# 7-segmentSchematic.net
KiCad netlist of a schematic drawn in Altium Designer
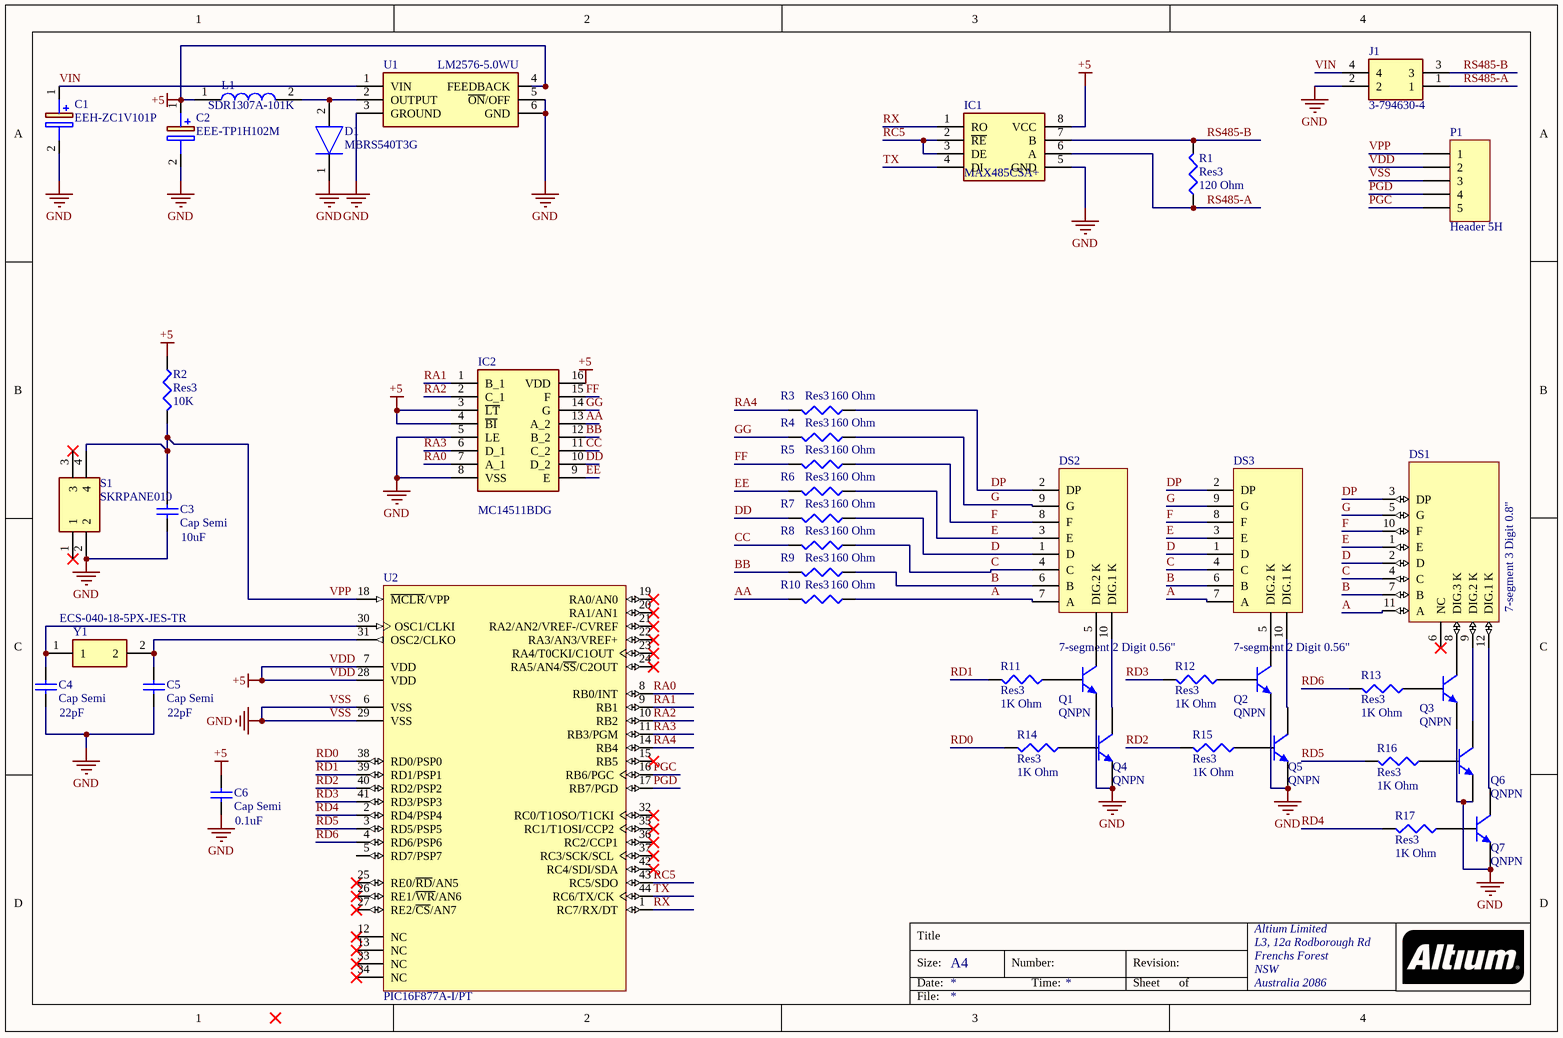
[diagram p0: 7-segmentSchematic.SchDoc]

(export (version "E")
  (design (tool "Eeschema 10.0.6"))
  (components
    (comp (ref "C1")
      (value "EEH-ZC1V101P")
      (footprint "SamacSys:CAPAE830X1050N")
      (description "Capacitor Polarised")
      (fields (field (name "MOUSER PART NUMBER") "667-EEH-ZC1V101P"))
      (libsource (lib "*") (part "EEH-ZC1V101P"))
    )
    (comp (ref "C2")
      (value "EEE-TP1H102M")
      (footprint "SamacSys:CAPAE1900X1700N")
      (description "Capacitor Polarised")
      (fields (field (name "MOUSER PART NUMBER") "667-EEE-TP1H102M"))
      (libsource (lib "*") (part "EEE-TP1H102M"))
    )
    (comp (ref "C3")
      (value "Cap Semi")
      (footprint "C1206")
      (description "Capacitor (Semiconductor SIM Model)")
      (fields (field (name "ALTIUM_VALUE") "10uF") (field (name "PUBLISHER") "Altium Limited"))
      (libsource (lib "Miscellaneous Devices") (part "Cap Semi"))
    )
    (comp (ref "C4")
      (value "Cap Semi")
      (footprint "C1206")
      (description "Capacitor (Semiconductor SIM Model)")
      (fields (field (name "ALTIUM_VALUE") "22pF") (field (name "PUBLISHER") "Altium Limited"))
      (libsource (lib "Miscellaneous Devices") (part "Cap Semi"))
    )
    (comp (ref "C5")
      (value "Cap Semi")
      (footprint "C1206")
      (description "Capacitor (Semiconductor SIM Model)")
      (fields (field (name "ALTIUM_VALUE") "22pF") (field (name "PUBLISHER") "Altium Limited"))
      (libsource (lib "Miscellaneous Devices") (part "Cap Semi"))
    )
    (comp (ref "C6")
      (value "Cap Semi")
      (footprint "C1206")
      (description "Capacitor (Semiconductor SIM Model)")
      (fields (field (name "ALTIUM_VALUE") "0.1uF") (field (name "PUBLISHER") "Altium Limited"))
      (libsource (lib "Miscellaneous Devices") (part "Cap Semi"))
    )
    (comp (ref "D1")
      (value "MBRS540T3G")
      (footprint "SamacSys:DIOM7958X256N")
      (description "Diode")
      (fields (field (name "MOUSER PART NUMBER") "863-MBRS540T3G") (field (name "RS PART NUMBER") "6880512P"))
      (libsource (lib "*") (part "MBRS540T3G"))
    )
    (comp (ref "DS1")
      (value "7-segment 3 Digit 0.8\"")
      (footprint "7-segment 3Digit")
      (libsource (lib "7-segment-3Digit") (part "7-segment 3 Digit"))
    )
    (comp (ref "DS2")
      (value "7-segment 2 Digit 0.56\"")
      (footprint "7-segment 2Digit")
      (libsource (lib "7-segment-3Digit") (part "7-segment 2 Digit"))
    )
    (comp (ref "DS3")
      (value "7-segment 2 Digit 0.56\"")
      (footprint "7-segment 2Digit")
      (libsource (lib "7-segment-3Digit") (part "7-segment 2 Digit"))
    )
    (comp (ref "IC1")
      (value "MAX485CSA+")
      (footprint "SamacSys:SOIC127P600X175-8N")
      (description "Integrated Circuit")
      (fields (field (name "MOUSER PART NUMBER") "700-MAX485CSA") (field (name "RS PART NUMBER") "5404564P"))
      (libsource (lib "*") (part "MAX485CSA+"))
    )
    (comp (ref "IC2")
      (value "MC14511BDG")
      (footprint "SamacSys:SOIC127P600X175-16N")
      (description "Integrated Circuit")
      (fields (field (name "MOUSER PART NUMBER") "863-MC14511BDG") (field (name "RS PART NUMBER") "8063267P"))
      (libsource (lib "*") (part "MC14511BDG"))
    )
    (comp (ref "J1")
      (value "3-794630-4")
      (footprint "SamacSys:37946304")
      (description "Connector")
      (fields (field (name "MOUSER PART NUMBER") "571-3-794630-4") (field (name "RS PART NUMBER") "4959344P"))
      (libsource (lib "*") (part "3-794630-4"))
    )
    (comp (ref "L1")
      (value "SDR1307A-101K")
      (footprint "SamacSys:SDR1307A101K")
      (description "Inductor")
      (fields (field (name "MOUSER PART NUMBER") "652-SDR1307A-101K"))
      (libsource (lib "*") (part "SDR1307A-101K"))
    )
    (comp (ref "P1")
      (value "Header 5H")
      (footprint "HDR1X5H")
      (description "Header, 5-Pin, Right Angle")
      (fields (field (name "PUBLISHER") "Altium Limited"))
      (libsource (lib "Miscellaneous Connectors") (part "Header 5H"))
    )
    (comp (ref "Q1")
      (value "QNPN")
      (footprint "SOT-23B_L")
      (description "NPN Bipolar Transistor")
      (fields (field (name "PUBLISHER") "Altium Limited"))
      (libsource (lib "Miscellaneous Devices") (part "QNPN"))
    )
    (comp (ref "Q2")
      (value "QNPN")
      (footprint "SOT-23B_L")
      (description "NPN Bipolar Transistor")
      (fields (field (name "PUBLISHER") "Altium Limited"))
      (libsource (lib "Miscellaneous Devices") (part "QNPN"))
    )
    (comp (ref "Q3")
      (value "QNPN")
      (footprint "SOT-23B_L")
      (description "NPN Bipolar Transistor")
      (fields (field (name "PUBLISHER") "Altium Limited"))
      (libsource (lib "Miscellaneous Devices") (part "QNPN"))
    )
    (comp (ref "Q4")
      (value "QNPN")
      (footprint "SOT-23B_L")
      (description "NPN Bipolar Transistor")
      (fields (field (name "PUBLISHER") "Altium Limited"))
      (libsource (lib "Miscellaneous Devices") (part "QNPN"))
    )
    (comp (ref "Q5")
      (value "QNPN")
      (footprint "SOT-23B_L")
      (description "NPN Bipolar Transistor")
      (fields (field (name "PUBLISHER") "Altium Limited"))
      (libsource (lib "Miscellaneous Devices") (part "QNPN"))
    )
    (comp (ref "Q6")
      (value "QNPN")
      (footprint "SOT-23B_L")
      (description "NPN Bipolar Transistor")
      (fields (field (name "PUBLISHER") "Altium Limited"))
      (libsource (lib "Miscellaneous Devices") (part "QNPN"))
    )
    (comp (ref "Q7")
      (value "QNPN")
      (footprint "SOT-23B_L")
      (description "NPN Bipolar Transistor")
      (fields (field (name "PUBLISHER") "Altium Limited"))
      (libsource (lib "Miscellaneous Devices") (part "QNPN"))
    )
    (comp (ref "R1")
      (value "Res3")
      (footprint "J1-0603")
      (description "Resistor")
      (fields (field (name "ALTIUM_VALUE") "120 Ohm") (field (name "PUBLISHER") "Altium Limited"))
      (libsource (lib "Miscellaneous Devices") (part "Res3"))
    )
    (comp (ref "R2")
      (value "Res3")
      (footprint "J1-0603")
      (description "Resistor")
      (fields (field (name "ALTIUM_VALUE") "10K") (field (name "PUBLISHER") "Altium Limited"))
      (libsource (lib "Miscellaneous Devices") (part "Res3"))
    )
    (comp (ref "R3")
      (value "Res3")
      (footprint "12Z-2010")
      (description "Resistor")
      (fields (field (name "ALTIUM_VALUE") "160 Ohm") (field (name "PUBLISHER") "Altium Limited"))
      (libsource (lib "Miscellaneous Devices") (part "Res3"))
    )
    (comp (ref "R4")
      (value "Res3")
      (footprint "12Z-2010")
      (description "Resistor")
      (fields (field (name "ALTIUM_VALUE") "160 Ohm") (field (name "PUBLISHER") "Altium Limited"))
      (libsource (lib "Miscellaneous Devices") (part "Res3"))
    )
    (comp (ref "R5")
      (value "Res3")
      (footprint "12Z-2010")
      (description "Resistor")
      (fields (field (name "ALTIUM_VALUE") "160 Ohm") (field (name "PUBLISHER") "Altium Limited"))
      (libsource (lib "Miscellaneous Devices") (part "Res3"))
    )
    (comp (ref "R6")
      (value "Res3")
      (footprint "12Z-2010")
      (description "Resistor")
      (fields (field (name "ALTIUM_VALUE") "160 Ohm") (field (name "PUBLISHER") "Altium Limited"))
      (libsource (lib "Miscellaneous Devices") (part "Res3"))
    )
    (comp (ref "R7")
      (value "Res3")
      (footprint "12Z-2010")
      (description "Resistor")
      (fields (field (name "ALTIUM_VALUE") "160 Ohm") (field (name "PUBLISHER") "Altium Limited"))
      (libsource (lib "Miscellaneous Devices") (part "Res3"))
    )
    (comp (ref "R8")
      (value "Res3")
      (footprint "12Z-2010")
      (description "Resistor")
      (fields (field (name "ALTIUM_VALUE") "160 Ohm") (field (name "PUBLISHER") "Altium Limited"))
      (libsource (lib "Miscellaneous Devices") (part "Res3"))
    )
    (comp (ref "R9")
      (value "Res3")
      (footprint "12Z-2010")
      (description "Resistor")
      (fields (field (name "ALTIUM_VALUE") "160 Ohm") (field (name "PUBLISHER") "Altium Limited"))
      (libsource (lib "Miscellaneous Devices") (part "Res3"))
    )
    (comp (ref "R10")
      (value "Res3")
      (footprint "12Z-2010")
      (description "Resistor")
      (fields (field (name "ALTIUM_VALUE") "160 Ohm") (field (name "PUBLISHER") "Altium Limited"))
      (libsource (lib "Miscellaneous Devices") (part "Res3"))
    )
    (comp (ref "R11")
      (value "Res3")
      (footprint "J1-0603")
      (description "Resistor")
      (fields (field (name "ALTIUM_VALUE") "1K Ohm") (field (name "PUBLISHER") "Altium Limited"))
      (libsource (lib "Miscellaneous Devices") (part "Res3"))
    )
    (comp (ref "R12")
      (value "Res3")
      (footprint "J1-0603")
      (description "Resistor")
      (fields (field (name "ALTIUM_VALUE") "1K Ohm") (field (name "PUBLISHER") "Altium Limited"))
      (libsource (lib "Miscellaneous Devices") (part "Res3"))
    )
    (comp (ref "R13")
      (value "Res3")
      (footprint "J1-0603")
      (description "Resistor")
      (fields (field (name "ALTIUM_VALUE") "1K Ohm") (field (name "PUBLISHER") "Altium Limited"))
      (libsource (lib "Miscellaneous Devices") (part "Res3"))
    )
    (comp (ref "R14")
      (value "Res3")
      (footprint "J1-0603")
      (description "Resistor")
      (fields (field (name "ALTIUM_VALUE") "1K Ohm") (field (name "PUBLISHER") "Altium Limited"))
      (libsource (lib "Miscellaneous Devices") (part "Res3"))
    )
    (comp (ref "R15")
      (value "Res3")
      (footprint "J1-0603")
      (description "Resistor")
      (fields (field (name "ALTIUM_VALUE") "1K Ohm") (field (name "PUBLISHER") "Altium Limited"))
      (libsource (lib "Miscellaneous Devices") (part "Res3"))
    )
    (comp (ref "R16")
      (value "Res3")
      (footprint "J1-0603")
      (description "Resistor")
      (fields (field (name "ALTIUM_VALUE") "1K Ohm") (field (name "PUBLISHER") "Altium Limited"))
      (libsource (lib "Miscellaneous Devices") (part "Res3"))
    )
    (comp (ref "R17")
      (value "Res3")
      (footprint "J1-0603")
      (description "Resistor")
      (fields (field (name "ALTIUM_VALUE") "1K Ohm") (field (name "PUBLISHER") "Altium Limited"))
      (libsource (lib "Miscellaneous Devices") (part "Res3"))
    )
    (comp (ref "S1")
      (value "SKRPANE010")
      (footprint "SamacSys:SKRPADE010")
      (description "Switch")
      (fields (field (name "MOUSER PART NUMBER") "688-SKRPANE010"))
      (libsource (lib "*") (part "SKRPANE010"))
    )
    (comp (ref "U1")
      (value "LM2576-5.0WU")
      (footprint "SamacSys:MICROCHIP_TO-263")
      (description "Undefined or Miscellaneous")
      (fields
        (field (name "MOUSER PART NUMBER") "998-LM2576-5.0WU")
        (field (name "RS PART NUMBER") "9101925P")
      )
      (libsource (lib "*") (part "LM2576-5.0WU"))
    )
    (comp (ref "U2")
      (value "PIC16F877A-I/PT")
      (footprint "TQFP-PT44_N")
      (fields (field (name "PUBLISHER") "Altium Limited"))
      (libsource (lib "Microchip Microcontroller 8-Bit PIC16") (part "PIC16F877A-I/PT"))
    )
    (comp (ref "Y1")
      (value "ECS-040-18-5PX-JES-TR")
      (footprint "SamacSys:ECS49205PXTR")
      (description "Crystal or Oscillator")
      (fields (field (name "MOUSER PART NUMBER") "520-040-18-5PX-JEST"))
      (libsource (lib "*") (part "ECS-040-18-5PX-JES-TR"))
    )
  )
  (nets
    (net (code "1") (name "+5") (class "Default")
      (node (ref "C2") (pin "1") (pinfunction "+_1") (pintype "passive"))
      (node (ref "C6") (pin "2") (pinfunction "2_2") (pintype "passive"))
      (node (ref "IC1") (pin "8") (pinfunction "VCC_8") (pintype "power_in"))
      (node (ref "IC2") (pin "16") (pinfunction "VDD_16") (pintype "power_in"))
      (node (ref "IC2") (pin "3") (pinfunction "~{LT}_3") (pintype "passive"))
      (node (ref "IC2") (pin "4") (pinfunction "~{BI}_4") (pintype "passive"))
      (node (ref "L1") (pin "1") (pinfunction "1_1") (pintype "passive"))
      (node (ref "P1") (pin "2") (pinfunction "2_2") (pintype "passive"))
      (node (ref "R2") (pin "1") (pinfunction "1_1") (pintype "passive"))
      (node (ref "U1") (pin "4") (pinfunction "FEEDBACK_4") (pintype "passive"))
      (node (ref "U2") (pin "28") (pinfunction "VDD_28") (pintype "power_in"))
      (node (ref "U2") (pin "7") (pinfunction "VDD_7") (pintype "power_in"))
    )
    (net (code "2") (name "/A") (class "Default")
      (node (ref "DS1") (pin "11") (pinfunction "A_11") (pintype "bidirectional"))
      (node (ref "DS2") (pin "7") (pinfunction "A_7") (pintype "passive"))
      (node (ref "DS3") (pin "7") (pinfunction "A_7") (pintype "passive"))
      (node (ref "R10") (pin "1") (pinfunction "1_1") (pintype "passive"))
    )
    (net (code "3") (name "/AA") (class "Default")
      (node (ref "IC2") (pin "13") (pinfunction "A_2_13") (pintype "passive"))
      (node (ref "R10") (pin "2") (pinfunction "2_2") (pintype "passive"))
    )
    (net (code "4") (name "/B") (class "Default")
      (node (ref "DS1") (pin "7") (pinfunction "B_7") (pintype "bidirectional"))
      (node (ref "DS2") (pin "6") (pinfunction "B_6") (pintype "passive"))
      (node (ref "DS3") (pin "6") (pinfunction "B_6") (pintype "passive"))
      (node (ref "R9") (pin "1") (pinfunction "1_1") (pintype "passive"))
    )
    (net (code "5") (name "/BB") (class "Default")
      (node (ref "IC2") (pin "12") (pinfunction "B_2_12") (pintype "passive"))
      (node (ref "R9") (pin "2") (pinfunction "2_2") (pintype "passive"))
    )
    (net (code "6") (name "/C") (class "Default")
      (node (ref "DS1") (pin "4") (pinfunction "C_4") (pintype "bidirectional"))
      (node (ref "DS2") (pin "4") (pinfunction "C_4") (pintype "passive"))
      (node (ref "DS3") (pin "4") (pinfunction "C_4") (pintype "passive"))
      (node (ref "R8") (pin "1") (pinfunction "1_1") (pintype "passive"))
    )
    (net (code "7") (name "/CC") (class "Default")
      (node (ref "IC2") (pin "11") (pinfunction "C_2_11") (pintype "passive"))
      (node (ref "R8") (pin "2") (pinfunction "2_2") (pintype "passive"))
    )
    (net (code "8") (name "/D") (class "Default")
      (node (ref "DS1") (pin "2") (pinfunction "D_2") (pintype "bidirectional"))
      (node (ref "DS2") (pin "1") (pinfunction "D_1") (pintype "passive"))
      (node (ref "DS3") (pin "1") (pinfunction "D_1") (pintype "passive"))
      (node (ref "R7") (pin "1") (pinfunction "1_1") (pintype "passive"))
    )
    (net (code "9") (name "/DD") (class "Default")
      (node (ref "IC2") (pin "10") (pinfunction "D_2_10") (pintype "passive"))
      (node (ref "R7") (pin "2") (pinfunction "2_2") (pintype "passive"))
    )
    (net (code "10") (name "/DP") (class "Default")
      (node (ref "DS1") (pin "3") (pinfunction "DP_3") (pintype "bidirectional"))
      (node (ref "DS2") (pin "2") (pinfunction "DP_2") (pintype "passive"))
      (node (ref "DS3") (pin "2") (pinfunction "DP_2") (pintype "passive"))
      (node (ref "R3") (pin "1") (pinfunction "1_1") (pintype "passive"))
    )
    (net (code "11") (name "/E") (class "Default")
      (node (ref "DS1") (pin "1") (pinfunction "E_1") (pintype "bidirectional"))
      (node (ref "DS2") (pin "3") (pinfunction "E_3") (pintype "passive"))
      (node (ref "DS3") (pin "3") (pinfunction "E_3") (pintype "passive"))
      (node (ref "R6") (pin "1") (pinfunction "1_1") (pintype "passive"))
    )
    (net (code "12") (name "/EE") (class "Default")
      (node (ref "IC2") (pin "9") (pinfunction "E_9") (pintype "passive"))
      (node (ref "R6") (pin "2") (pinfunction "2_2") (pintype "passive"))
    )
    (net (code "13") (name "/F") (class "Default")
      (node (ref "DS1") (pin "10") (pinfunction "F_10") (pintype "bidirectional"))
      (node (ref "DS2") (pin "8") (pinfunction "F_8") (pintype "passive"))
      (node (ref "DS3") (pin "8") (pinfunction "F_8") (pintype "passive"))
      (node (ref "R5") (pin "1") (pinfunction "1_1") (pintype "passive"))
    )
    (net (code "14") (name "/FF") (class "Default")
      (node (ref "IC2") (pin "15") (pinfunction "F_15") (pintype "passive"))
      (node (ref "R5") (pin "2") (pinfunction "2_2") (pintype "passive"))
    )
    (net (code "15") (name "/G") (class "Default")
      (node (ref "DS1") (pin "5") (pinfunction "G_5") (pintype "bidirectional"))
      (node (ref "DS2") (pin "9") (pinfunction "G_9") (pintype "passive"))
      (node (ref "DS3") (pin "9") (pinfunction "G_9") (pintype "passive"))
      (node (ref "R4") (pin "1") (pinfunction "1_1") (pintype "passive"))
    )
    (net (code "16") (name "/GG") (class "Default")
      (node (ref "IC2") (pin "14") (pinfunction "G_14") (pintype "passive"))
      (node (ref "R4") (pin "2") (pinfunction "2_2") (pintype "passive"))
    )
    (net (code "17") (name "/PGC") (class "Default")
      (node (ref "P1") (pin "5") (pinfunction "5_5") (pintype "passive"))
      (node (ref "U2") (pin "16") (pinfunction "RB6/PGC_16") (pintype "bidirectional"))
    )
    (net (code "18") (name "/PGD") (class "Default")
      (node (ref "P1") (pin "4") (pinfunction "4_4") (pintype "passive"))
      (node (ref "U2") (pin "17") (pinfunction "RB7/PGD_17") (pintype "bidirectional"))
    )
    (net (code "19") (name "/RA0") (class "Default")
      (node (ref "IC2") (pin "7") (pinfunction "A_1_7") (pintype "passive"))
      (node (ref "U2") (pin "8") (pinfunction "RB0/INT_8") (pintype "bidirectional"))
    )
    (net (code "20") (name "/RA1") (class "Default")
      (node (ref "IC2") (pin "1") (pinfunction "B_1_1") (pintype "passive"))
      (node (ref "U2") (pin "9") (pinfunction "RB1_9") (pintype "bidirectional"))
    )
    (net (code "21") (name "/RA2") (class "Default")
      (node (ref "IC2") (pin "2") (pinfunction "C_1_2") (pintype "passive"))
      (node (ref "U2") (pin "10") (pinfunction "RB2_10") (pintype "bidirectional"))
    )
    (net (code "22") (name "/RA3") (class "Default")
      (node (ref "IC2") (pin "6") (pinfunction "D_1_6") (pintype "passive"))
      (node (ref "U2") (pin "11") (pinfunction "RB3/PGM_11") (pintype "bidirectional"))
    )
    (net (code "23") (name "/RA4") (class "Default")
      (node (ref "R3") (pin "2") (pinfunction "2_2") (pintype "passive"))
      (node (ref "U2") (pin "14") (pinfunction "RB4_14") (pintype "bidirectional"))
    )
    (net (code "24") (name "/RC5") (class "Default")
      (node (ref "IC1") (pin "2") (pinfunction "~{RE}_2") (pintype "passive"))
      (node (ref "IC1") (pin "3") (pinfunction "DE_3") (pintype "passive"))
      (node (ref "U2") (pin "43") (pinfunction "RC5/SDO_43") (pintype "bidirectional"))
    )
    (net (code "25") (name "/RD0") (class "Default")
      (node (ref "R14") (pin "2") (pinfunction "2_2") (pintype "passive"))
      (node (ref "U2") (pin "38") (pinfunction "RD0/PSP0_38") (pintype "bidirectional"))
    )
    (net (code "26") (name "/RD1") (class "Default")
      (node (ref "R11") (pin "2") (pinfunction "2_2") (pintype "passive"))
      (node (ref "U2") (pin "39") (pinfunction "RD1/PSP1_39") (pintype "bidirectional"))
    )
    (net (code "27") (name "/RD2") (class "Default")
      (node (ref "R15") (pin "2") (pinfunction "2_2") (pintype "passive"))
      (node (ref "U2") (pin "40") (pinfunction "RD2/PSP2_40") (pintype "bidirectional"))
    )
    (net (code "28") (name "/RD3") (class "Default")
      (node (ref "R12") (pin "2") (pinfunction "2_2") (pintype "passive"))
      (node (ref "U2") (pin "41") (pinfunction "RD3/PSP3_41") (pintype "bidirectional"))
    )
    (net (code "29") (name "/RD4") (class "Default")
      (node (ref "R17") (pin "2") (pinfunction "2_2") (pintype "passive"))
      (node (ref "U2") (pin "2") (pinfunction "RD4/PSP4_2") (pintype "bidirectional"))
    )
    (net (code "30") (name "/RD5") (class "Default")
      (node (ref "R16") (pin "2") (pinfunction "2_2") (pintype "passive"))
      (node (ref "U2") (pin "3") (pinfunction "RD5/PSP5_3") (pintype "bidirectional"))
    )
    (net (code "31") (name "/RD6") (class "Default")
      (node (ref "R13") (pin "2") (pinfunction "2_2") (pintype "passive"))
      (node (ref "U2") (pin "4") (pinfunction "RD6/PSP6_4") (pintype "bidirectional"))
    )
    (net (code "32") (name "/RS485-A") (class "Default")
      (node (ref "IC1") (pin "6") (pinfunction "A_6") (pintype "passive"))
      (node (ref "J1") (pin "1") (pinfunction "1_1") (pintype "passive"))
      (node (ref "R1") (pin "1") (pinfunction "1_1") (pintype "passive"))
    )
    (net (code "33") (name "/RS485-B") (class "Default")
      (node (ref "IC1") (pin "7") (pinfunction "B_7") (pintype "passive"))
      (node (ref "J1") (pin "3") (pinfunction "3_3") (pintype "passive"))
      (node (ref "R1") (pin "2") (pinfunction "2_2") (pintype "passive"))
    )
    (net (code "34") (name "/RX") (class "Default")
      (node (ref "IC1") (pin "1") (pinfunction "RO_1") (pintype "passive"))
      (node (ref "U2") (pin "1") (pinfunction "RC7/RX/DT_1") (pintype "bidirectional"))
    )
    (net (code "35") (name "/TX") (class "Default")
      (node (ref "IC1") (pin "4") (pinfunction "DI_4") (pintype "passive"))
      (node (ref "U2") (pin "44") (pinfunction "RC6/TX/CK_44") (pintype "bidirectional"))
    )
    (net (code "36") (name "/VIN") (class "Default")
      (node (ref "C1") (pin "1") (pinfunction "+_1") (pintype "passive"))
      (node (ref "J1") (pin "4") (pinfunction "4_4") (pintype "passive"))
      (node (ref "U1") (pin "1") (pinfunction "VIN_1") (pintype "passive"))
    )
    (net (code "37") (name "/VPP") (class "Default")
      (node (ref "C3") (pin "2") (pinfunction "2_2") (pintype "passive"))
      (node (ref "P1") (pin "1") (pinfunction "1_1") (pintype "passive"))
      (node (ref "R2") (pin "2") (pinfunction "2_2") (pintype "passive"))
      (node (ref "S1") (pin "4") (pinfunction "4_4") (pintype "passive"))
      (node (ref "U2") (pin "18") (pinfunction "~{MCLR}/VPP_18") (pintype "input"))
    )
    (net (code "38") (name "GND") (class "Default")
      (node (ref "C1") (pin "2") (pinfunction "-_2") (pintype "passive"))
      (node (ref "C2") (pin "2") (pinfunction "-_2") (pintype "passive"))
      (node (ref "C3") (pin "1") (pinfunction "1_1") (pintype "passive"))
      (node (ref "C4") (pin "1") (pinfunction "1_1") (pintype "passive"))
      (node (ref "C5") (pin "1") (pinfunction "1_1") (pintype "passive"))
      (node (ref "C6") (pin "1") (pinfunction "1_1") (pintype "passive"))
      (node (ref "D1") (pin "1") (pinfunction "K_1") (pintype "passive"))
      (node (ref "IC1") (pin "5") (pinfunction "GND_5") (pintype "power_in"))
      (node (ref "IC2") (pin "5") (pinfunction "LE_5") (pintype "passive"))
      (node (ref "IC2") (pin "8") (pinfunction "VSS_8") (pintype "power_in"))
      (node (ref "J1") (pin "2") (pinfunction "2_2") (pintype "passive"))
      (node (ref "P1") (pin "3") (pinfunction "3_3") (pintype "passive"))
      (node (ref "Q1") (pin "3") (pinfunction "E_3") (pintype "passive"))
      (node (ref "Q2") (pin "3") (pinfunction "E_3") (pintype "passive"))
      (node (ref "Q3") (pin "3") (pinfunction "E_3") (pintype "passive"))
      (node (ref "Q4") (pin "3") (pinfunction "E_3") (pintype "passive"))
      (node (ref "Q5") (pin "3") (pinfunction "E_3") (pintype "passive"))
      (node (ref "Q6") (pin "3") (pinfunction "E_3") (pintype "passive"))
      (node (ref "Q7") (pin "3") (pinfunction "E_3") (pintype "passive"))
      (node (ref "S1") (pin "2") (pinfunction "2_2") (pintype "passive"))
      (node (ref "U1") (pin "3") (pinfunction "GROUND_3") (pintype "passive"))
      (node (ref "U1") (pin "5") (pinfunction "~{ON}/OFF_5") (pintype "passive"))
      (node (ref "U1") (pin "6") (pinfunction "GND_6") (pintype "passive"))
      (node (ref "U2") (pin "29") (pinfunction "VSS_29") (pintype "power_in"))
      (node (ref "U2") (pin "6") (pinfunction "VSS_6") (pintype "power_in"))
    )
    (net (code "39") (name "Net-(D1-A)") (class "Default")
      (node (ref "D1") (pin "2") (pinfunction "A_2") (pintype "passive"))
      (node (ref "L1") (pin "2") (pinfunction "2_2") (pintype "passive"))
      (node (ref "U1") (pin "2") (pinfunction "OUTPUT_2") (pintype "passive"))
    )
    (net (code "40") (name "Net-(DS1-DIG.1_K)") (class "Default")
      (node (ref "DS1") (pin "12") (pinfunction "DIG.1_K_12") (pintype "bidirectional"))
      (node (ref "Q7") (pin "1") (pinfunction "C_1") (pintype "passive"))
    )
    (net (code "41") (name "Net-(DS1-DIG.2_K)") (class "Default")
      (node (ref "DS1") (pin "9") (pinfunction "DIG.2_K_9") (pintype "bidirectional"))
      (node (ref "Q6") (pin "1") (pinfunction "C_1") (pintype "passive"))
    )
    (net (code "42") (name "Net-(DS1-DIG.3_K)") (class "Default")
      (node (ref "DS1") (pin "8") (pinfunction "DIG.3_K_8") (pintype "bidirectional"))
      (node (ref "Q3") (pin "1") (pinfunction "C_1") (pintype "passive"))
    )
    (net (code "43") (name "Net-(DS2-DIG.1_K)") (class "Default")
      (node (ref "DS2") (pin "10") (pinfunction "DIG.1_K_10") (pintype "passive"))
      (node (ref "Q4") (pin "1") (pinfunction "C_1") (pintype "passive"))
    )
    (net (code "44") (name "Net-(DS2-DIG.2_K)") (class "Default")
      (node (ref "DS2") (pin "5") (pinfunction "DIG.2_K_5") (pintype "passive"))
      (node (ref "Q1") (pin "1") (pinfunction "C_1") (pintype "passive"))
    )
    (net (code "45") (name "Net-(DS3-DIG.1_K)") (class "Default")
      (node (ref "DS3") (pin "10") (pinfunction "DIG.1_K_10") (pintype "passive"))
      (node (ref "Q5") (pin "1") (pinfunction "C_1") (pintype "passive"))
    )
    (net (code "46") (name "Net-(DS3-DIG.2_K)") (class "Default")
      (node (ref "DS3") (pin "5") (pinfunction "DIG.2_K_5") (pintype "passive"))
      (node (ref "Q2") (pin "1") (pinfunction "C_1") (pintype "passive"))
    )
    (net (code "47") (name "Net-(Q1-B)") (class "Default")
      (node (ref "Q1") (pin "2") (pinfunction "B_2") (pintype "passive"))
      (node (ref "R11") (pin "1") (pinfunction "1_1") (pintype "passive"))
    )
    (net (code "48") (name "Net-(Q2-B)") (class "Default")
      (node (ref "Q2") (pin "2") (pinfunction "B_2") (pintype "passive"))
      (node (ref "R12") (pin "1") (pinfunction "1_1") (pintype "passive"))
    )
    (net (code "49") (name "Net-(Q3-B)") (class "Default")
      (node (ref "Q3") (pin "2") (pinfunction "B_2") (pintype "passive"))
      (node (ref "R13") (pin "1") (pinfunction "1_1") (pintype "passive"))
    )
    (net (code "50") (name "Net-(Q4-B)") (class "Default")
      (node (ref "Q4") (pin "2") (pinfunction "B_2") (pintype "passive"))
      (node (ref "R14") (pin "1") (pinfunction "1_1") (pintype "passive"))
    )
    (net (code "51") (name "Net-(Q5-B)") (class "Default")
      (node (ref "Q5") (pin "2") (pinfunction "B_2") (pintype "passive"))
      (node (ref "R15") (pin "1") (pinfunction "1_1") (pintype "passive"))
    )
    (net (code "52") (name "Net-(Q6-B)") (class "Default")
      (node (ref "Q6") (pin "2") (pinfunction "B_2") (pintype "passive"))
      (node (ref "R16") (pin "1") (pinfunction "1_1") (pintype "passive"))
    )
    (net (code "53") (name "Net-(Q7-B)") (class "Default")
      (node (ref "Q7") (pin "2") (pinfunction "B_2") (pintype "passive"))
      (node (ref "R17") (pin "1") (pinfunction "1_1") (pintype "passive"))
    )
    (net (code "54") (name "Net-(U2-OSC1{slash}CLKI)") (class "Default")
      (node (ref "C4") (pin "2") (pinfunction "2_2") (pintype "passive"))
      (node (ref "U2") (pin "30") (pinfunction "OSC1/CLKI_30") (pintype "input"))
      (node (ref "Y1") (pin "1") (pinfunction "1_1") (pintype "passive"))
    )
    (net (code "55") (name "Net-(U2-OSC2{slash}CLKO)") (class "Default")
      (node (ref "C5") (pin "2") (pinfunction "2_2") (pintype "passive"))
      (node (ref "U2") (pin "31") (pinfunction "OSC2/CLKO_31") (pintype "output"))
      (node (ref "Y1") (pin "2") (pinfunction "2_2") (pintype "passive"))
    )
    (net (code "56") (name "unconnected-(DS1-NC-Pad6)") (class "Default")
      (node (ref "DS1") (pin "6") (pinfunction "NC_6") (pintype "passive+no_connect"))
    )
    (net (code "57") (name "unconnected-(S1-Pad1)") (class "Default")
      (node (ref "S1") (pin "1") (pinfunction "1_1") (pintype "passive+no_connect"))
    )
    (net (code "58") (name "unconnected-(S1-Pad3)") (class "Default")
      (node (ref "S1") (pin "3") (pinfunction "3_3") (pintype "passive+no_connect"))
    )
    (net (code "59") (name "unconnected-(U2-NC-Pad12)") (class "Default")
      (node (ref "U2") (pin "12") (pinfunction "NC_12") (pintype "passive+no_connect"))
    )
    (net (code "60") (name "unconnected-(U2-NC-Pad13)") (class "Default")
      (node (ref "U2") (pin "13") (pinfunction "NC_13") (pintype "passive+no_connect"))
    )
    (net (code "61") (name "unconnected-(U2-NC-Pad33)") (class "Default")
      (node (ref "U2") (pin "33") (pinfunction "NC_33") (pintype "passive+no_connect"))
    )
    (net (code "62") (name "unconnected-(U2-NC-Pad34)") (class "Default")
      (node (ref "U2") (pin "34") (pinfunction "NC_34") (pintype "passive+no_connect"))
    )
    (net (code "63") (name "unconnected-(U2-RA0{slash}AN0-Pad19)") (class "Default")
      (node (ref "U2") (pin "19") (pinfunction "RA0/AN0_19") (pintype "bidirectional+no_connect"))
    )
    (net (code "64") (name "unconnected-(U2-RA1{slash}AN1-Pad20)") (class "Default")
      (node (ref "U2") (pin "20") (pinfunction "RA1/AN1_20") (pintype "bidirectional+no_connect"))
    )
    (net (code "65") (name "unconnected-(U2-RA2{slash}AN2{slash}VREF-{slash}CVREF-Pad21)") (class "Default")
      (node (ref "U2") (pin "21") (pinfunction "RA2/AN2/VREF-/CVREF_21") (pintype "bidirectional+no_connect"))
    )
    (net (code "66") (name "unconnected-(U2-RA3{slash}AN3{slash}VREF+-Pad22)") (class "Default")
      (node (ref "U2") (pin "22") (pinfunction "RA3/AN3/VREF+_22") (pintype "bidirectional+no_connect"))
    )
    (net (code "67") (name "unconnected-(U2-RA4{slash}T0CKI{slash}C1OUT-Pad23)") (class "Default")
      (node (ref "U2") (pin "23") (pinfunction "RA4/T0CKI/C1OUT_23") (pintype "bidirectional+no_connect"))
    )
    (net (code "68") (name "unconnected-(U2-RA5{slash}AN4{slash}~{SS}{slash}C2OUT-Pad24)") (class "Default")
      (node (ref "U2") (pin "24") (pinfunction "RA5/AN4/~{SS}/C2OUT_24") (pintype "bidirectional+no_connect"))
    )
    (net (code "69") (name "unconnected-(U2-RB5-Pad15)") (class "Default")
      (node (ref "U2") (pin "15") (pinfunction "RB5_15") (pintype "bidirectional+no_connect"))
    )
    (net (code "70") (name "unconnected-(U2-RC0{slash}T1OSO{slash}T1CKI-Pad32)") (class "Default")
      (node (ref "U2") (pin "32") (pinfunction "RC0/T1OSO/T1CKI_32") (pintype "bidirectional+no_connect"))
    )
    (net (code "71") (name "unconnected-(U2-RC1{slash}T1OSI{slash}CCP2-Pad35)") (class "Default")
      (node (ref "U2") (pin "35") (pinfunction "RC1/T1OSI/CCP2_35") (pintype "bidirectional+no_connect"))
    )
    (net (code "72") (name "unconnected-(U2-RC2{slash}CCP1-Pad36)") (class "Default")
      (node (ref "U2") (pin "36") (pinfunction "RC2/CCP1_36") (pintype "bidirectional+no_connect"))
    )
    (net (code "73") (name "unconnected-(U2-RC3{slash}SCK{slash}SCL-Pad37)") (class "Default")
      (node (ref "U2") (pin "37") (pinfunction "RC3/SCK/SCL_37") (pintype "bidirectional+no_connect"))
    )
    (net (code "74") (name "unconnected-(U2-RC4{slash}SDI{slash}SDA-Pad42)") (class "Default")
      (node (ref "U2") (pin "42") (pinfunction "RC4/SDI/SDA_42") (pintype "bidirectional+no_connect"))
    )
    (net (code "75") (name "unconnected-(U2-RD7{slash}PSP7-Pad5)") (class "Default")
      (node (ref "U2") (pin "5") (pinfunction "RD7/PSP7_5") (pintype "bidirectional"))
    )
    (net (code "76") (name "unconnected-(U2-RE0{slash}~{RD}{slash}AN5-Pad25)") (class "Default")
      (node (ref "U2") (pin "25") (pinfunction "RE0/~{RD}/AN5_25") (pintype "bidirectional+no_connect"))
    )
    (net (code "77") (name "unconnected-(U2-RE1{slash}~{WR}{slash}AN6-Pad26)") (class "Default")
      (node (ref "U2") (pin "26") (pinfunction "RE1/~{WR}/AN6_26") (pintype "bidirectional+no_connect"))
    )
    (net (code "78") (name "unconnected-(U2-RE2{slash}~{CS}{slash}AN7-Pad27)") (class "Default")
      (node (ref "U2") (pin "27") (pinfunction "RE2/~{CS}/AN7_27") (pintype "bidirectional+no_connect"))
    )
  )
)
